# Mach_trai_tim.net
KiCad netlist of a schematic drawn in Altium Designer
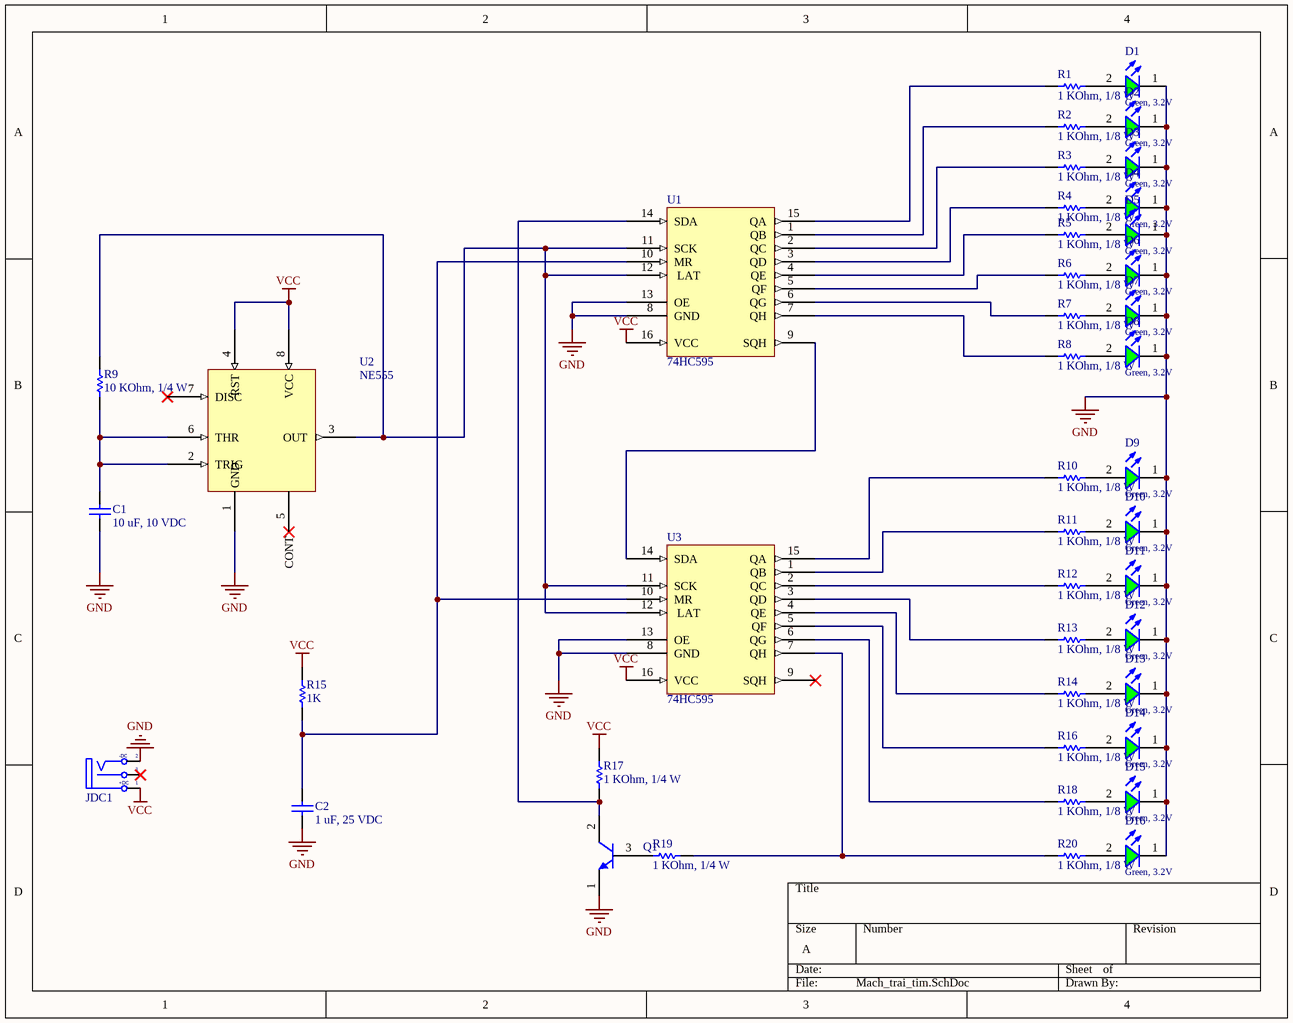
[diagram p0: Mach_trai_tim.SchDoc]

(export (version "E")
  (design (tool "Eeschema 10.0.6"))
  (components
    (comp (ref "C1")
      (value "10 uF, 10 VDC")
      (footprint "CAP_0603")
      (description "CAP, size 0603, 10 uF, 10 VDC")
      (fields (field (name "TOLERANCE") "+/-10%"))
      (libsource (lib "Altium_Ceramic_Cap") (part "0106031061010"))
    )
    (comp (ref "C2")
      (value "1 uF, 25 VDC")
      (footprint "CAP_0603")
      (description "CAP, size 0603, 1 uF, 25 VDC")
      (fields (field (name "TOLERANCE") "+/-10%"))
      (libsource (lib "Altium_Ceramic_Cap") (part "0106031051025"))
    )
    (comp (ref "D1")
      (value "Green, 3.2V")
      (footprint "WL-SMCW_0805")
      (description "WL-SMCW SMT Mono-color Chip LED Waterclear, size 0805, Green, 3.2V, 140deg")
      (libsource (lib "Altium_LED") (part "160805GreenClear"))
    )
    (comp (ref "D2")
      (value "Green, 3.2V")
      (footprint "WL-SMCW_0805")
      (description "WL-SMCW SMT Mono-color Chip LED Waterclear, size 0805, Green, 3.2V, 140deg")
      (libsource (lib "Altium_LED") (part "160805GreenClear"))
    )
    (comp (ref "D3")
      (value "Green, 3.2V")
      (footprint "WL-SMCW_0805")
      (description "WL-SMCW SMT Mono-color Chip LED Waterclear, size 0805, Green, 3.2V, 140deg")
      (libsource (lib "Altium_LED") (part "160805GreenClear"))
    )
    (comp (ref "D4")
      (value "Green, 3.2V")
      (footprint "WL-SMCW_0805")
      (description "WL-SMCW SMT Mono-color Chip LED Waterclear, size 0805, Green, 3.2V, 140deg")
      (libsource (lib "Altium_LED") (part "160805GreenClear"))
    )
    (comp (ref "D5")
      (value "Green, 3.2V")
      (footprint "WL-SMCW_0805")
      (description "WL-SMCW SMT Mono-color Chip LED Waterclear, size 0805, Green, 3.2V, 140deg")
      (libsource (lib "Altium_LED") (part "160805GreenClear"))
    )
    (comp (ref "D6")
      (value "Green, 3.2V")
      (footprint "WL-SMCW_0805")
      (description "WL-SMCW SMT Mono-color Chip LED Waterclear, size 0805, Green, 3.2V, 140deg")
      (libsource (lib "Altium_LED") (part "160805GreenClear"))
    )
    (comp (ref "D7")
      (value "Green, 3.2V")
      (footprint "WL-SMCW_0805")
      (description "WL-SMCW SMT Mono-color Chip LED Waterclear, size 0805, Green, 3.2V, 140deg")
      (libsource (lib "Altium_LED") (part "160805GreenClear"))
    )
    (comp (ref "D8")
      (value "Green, 3.2V")
      (footprint "WL-SMCW_0805")
      (description "WL-SMCW SMT Mono-color Chip LED Waterclear, size 0805, Green, 3.2V, 140deg")
      (libsource (lib "Altium_LED") (part "160805GreenClear"))
    )
    (comp (ref "D9")
      (value "Green, 3.2V")
      (footprint "WL-SMCW_0805")
      (description "WL-SMCW SMT Mono-color Chip LED Waterclear, size 0805, Green, 3.2V, 140deg")
      (libsource (lib "Altium_LED") (part "160805GreenClear"))
    )
    (comp (ref "D10")
      (value "Green, 3.2V")
      (footprint "WL-SMCW_0805")
      (description "WL-SMCW SMT Mono-color Chip LED Waterclear, size 0805, Green, 3.2V, 140deg")
      (libsource (lib "Altium_LED") (part "160805GreenClear"))
    )
    (comp (ref "D11")
      (value "Green, 3.2V")
      (footprint "WL-SMCW_0805")
      (description "WL-SMCW SMT Mono-color Chip LED Waterclear, size 0805, Green, 3.2V, 140deg")
      (libsource (lib "Altium_LED") (part "160805GreenClear"))
    )
    (comp (ref "D12")
      (value "Green, 3.2V")
      (footprint "WL-SMCW_0805")
      (description "WL-SMCW SMT Mono-color Chip LED Waterclear, size 0805, Green, 3.2V, 140deg")
      (libsource (lib "Altium_LED") (part "160805GreenClear"))
    )
    (comp (ref "D13")
      (value "Green, 3.2V")
      (footprint "WL-SMCW_0805")
      (description "WL-SMCW SMT Mono-color Chip LED Waterclear, size 0805, Green, 3.2V, 140deg")
      (libsource (lib "Altium_LED") (part "160805GreenClear"))
    )
    (comp (ref "D14")
      (value "Green, 3.2V")
      (footprint "WL-SMCW_0805")
      (description "WL-SMCW SMT Mono-color Chip LED Waterclear, size 0805, Green, 3.2V, 140deg")
      (libsource (lib "Altium_LED") (part "160805GreenClear"))
    )
    (comp (ref "D15")
      (value "Green, 3.2V")
      (footprint "WL-SMCW_0805")
      (description "WL-SMCW SMT Mono-color Chip LED Waterclear, size 0805, Green, 3.2V, 140deg")
      (libsource (lib "Altium_LED") (part "160805GreenClear"))
    )
    (comp (ref "D16")
      (value "Green, 3.2V")
      (footprint "WL-SMCW_0805")
      (description "WL-SMCW SMT Mono-color Chip LED Waterclear, size 0805, Green, 3.2V, 140deg")
      (libsource (lib "Altium_LED") (part "160805GreenClear"))
    )
    (comp (ref "JDC1")
      (value "Jack DC")
      (footprint "DC-IN")
      (description "Jack DC input")
      (libsource (lib "PIF_Library") (part "Jack DC"))
    )
    (comp (ref "Q1")
      (value "C1815")
      (footprint "SOT23B")
      (description "NPN Bipolar Transistor")
      (libsource (lib "PIF_Library") (part "C1815"))
    )
    (comp (ref "R1")
      (value "1 KOhm, 1/8 W")
      (footprint "RESISTOR_0805")
      (description "RES, size 0805, 1 KOhm, 1/8 W")
      (libsource (lib "Altium_Resistor") (part "0008051021"))
    )
    (comp (ref "R2")
      (value "1 KOhm, 1/8 W")
      (footprint "RESISTOR_0805")
      (description "RES, size 0805, 1 KOhm, 1/8 W")
      (libsource (lib "Altium_Resistor") (part "0008051021"))
    )
    (comp (ref "R3")
      (value "1 KOhm, 1/8 W")
      (footprint "RESISTOR_0805")
      (description "RES, size 0805, 1 KOhm, 1/8 W")
      (libsource (lib "Altium_Resistor") (part "0008051021"))
    )
    (comp (ref "R4")
      (value "1 KOhm, 1/8 W")
      (footprint "RESISTOR_0805")
      (description "RES, size 0805, 1 KOhm, 1/8 W")
      (libsource (lib "Altium_Resistor") (part "0008051021"))
    )
    (comp (ref "R5")
      (value "1 KOhm, 1/8 W")
      (footprint "RESISTOR_0805")
      (description "RES, size 0805, 1 KOhm, 1/8 W")
      (libsource (lib "Altium_Resistor") (part "0008051021"))
    )
    (comp (ref "R6")
      (value "1 KOhm, 1/8 W")
      (footprint "RESISTOR_0805")
      (description "RES, size 0805, 1 KOhm, 1/8 W")
      (libsource (lib "Altium_Resistor") (part "0008051021"))
    )
    (comp (ref "R7")
      (value "1 KOhm, 1/8 W")
      (footprint "RESISTOR_0805")
      (description "RES, size 0805, 1 KOhm, 1/8 W")
      (libsource (lib "Altium_Resistor") (part "0008051021"))
    )
    (comp (ref "R8")
      (value "1 KOhm, 1/8 W")
      (footprint "RESISTOR_0805")
      (description "RES, size 0805, 1 KOhm, 1/8 W")
      (libsource (lib "Altium_Resistor") (part "0008051021"))
    )
    (comp (ref "R9")
      (value "10 KOhm, 1/4 W")
      (footprint "resistor_0603")
      (description "RES, size 0603, 10 KOhm, 1/4 W")
      (libsource (lib "Altium_Resistor") (part "0006031031"))
    )
    (comp (ref "R10")
      (value "1 KOhm, 1/8 W")
      (footprint "RESISTOR_0805")
      (description "RES, size 0805, 1 KOhm, 1/8 W")
      (libsource (lib "Altium_Resistor") (part "0008051021"))
    )
    (comp (ref "R11")
      (value "1 KOhm, 1/8 W")
      (footprint "RESISTOR_0805")
      (description "RES, size 0805, 1 KOhm, 1/8 W")
      (libsource (lib "Altium_Resistor") (part "0008051021"))
    )
    (comp (ref "R12")
      (value "1 KOhm, 1/8 W")
      (footprint "RESISTOR_0805")
      (description "RES, size 0805, 1 KOhm, 1/8 W")
      (libsource (lib "Altium_Resistor") (part "0008051021"))
    )
    (comp (ref "R13")
      (value "1 KOhm, 1/8 W")
      (footprint "RESISTOR_0805")
      (description "RES, size 0805, 1 KOhm, 1/8 W")
      (libsource (lib "Altium_Resistor") (part "0008051021"))
    )
    (comp (ref "R14")
      (value "1 KOhm, 1/8 W")
      (footprint "RESISTOR_0805")
      (description "RES, size 0805, 1 KOhm, 1/8 W")
      (libsource (lib "Altium_Resistor") (part "0008051021"))
    )
    (comp (ref "R15")
      (value "1K")
      (footprint "RES-SM-0603")
      (description "Resistor")
      (fields (field (name "Comment") "RESISTOR SMD"))
      (libsource (lib "PIF_Library") (part "RESISTOR SMD"))
    )
    (comp (ref "R16")
      (value "1 KOhm, 1/8 W")
      (footprint "RESISTOR_0805")
      (description "RES, size 0805, 1 KOhm, 1/8 W")
      (libsource (lib "Altium_Resistor") (part "0008051021"))
    )
    (comp (ref "R17")
      (value "1 KOhm, 1/4 W")
      (footprint "resistor_0603")
      (description "RES, size 0603, 1 KOhm, 1/4 W")
      (libsource (lib "Altium_Resistor") (part "0006031025"))
    )
    (comp (ref "R18")
      (value "1 KOhm, 1/8 W")
      (footprint "RESISTOR_0805")
      (description "RES, size 0805, 1 KOhm, 1/8 W")
      (libsource (lib "Altium_Resistor") (part "0008051021"))
    )
    (comp (ref "R19")
      (value "1 KOhm, 1/4 W")
      (footprint "resistor_0603")
      (description "RES, size 0603, 1 KOhm, 1/4 W")
      (libsource (lib "Altium_Resistor") (part "0006031025"))
    )
    (comp (ref "R20")
      (value "1 KOhm, 1/8 W")
      (footprint "RESISTOR_0805")
      (description "RES, size 0805, 1 KOhm, 1/8 W")
      (libsource (lib "Altium_Resistor") (part "0008051021"))
    )
    (comp (ref "U1")
      (value "74HC595")
      (footprint "74HC595")
      (libsource (lib "Thư_viện_IC_Văn_20_2_2025") (part "74HC595"))
    )
    (comp (ref "U2")
      (value "NE555")
      (footprint "NE555")
      (libsource (lib "Thư_viện_IC_Văn_20_2_2025") (part "NE555"))
    )
    (comp (ref "U3")
      (value "74HC595")
      (footprint "74HC595")
      (libsource (lib "Thư_viện_IC_Văn_20_2_2025") (part "74HC595"))
    )
  )
  (nets
    (net (code "1") (name "GND") (class "Default")
      (node (ref "C1") (pin "1") (pinfunction "1_1") (pintype "passive"))
      (node (ref "C2") (pin "2") (pinfunction "2_2") (pintype "passive"))
      (node (ref "D1") (pin "1") (pinfunction "K_1") (pintype "passive"))
      (node (ref "D10") (pin "1") (pinfunction "K_1") (pintype "passive"))
      (node (ref "D11") (pin "1") (pinfunction "K_1") (pintype "passive"))
      (node (ref "D12") (pin "1") (pinfunction "K_1") (pintype "passive"))
      (node (ref "D13") (pin "1") (pinfunction "K_1") (pintype "passive"))
      (node (ref "D14") (pin "1") (pinfunction "K_1") (pintype "passive"))
      (node (ref "D15") (pin "1") (pinfunction "K_1") (pintype "passive"))
      (node (ref "D16") (pin "1") (pinfunction "K_1") (pintype "passive"))
      (node (ref "D2") (pin "1") (pinfunction "K_1") (pintype "passive"))
      (node (ref "D3") (pin "1") (pinfunction "K_1") (pintype "passive"))
      (node (ref "D4") (pin "1") (pinfunction "K_1") (pintype "passive"))
      (node (ref "D5") (pin "1") (pinfunction "K_1") (pintype "passive"))
      (node (ref "D6") (pin "1") (pinfunction "K_1") (pintype "passive"))
      (node (ref "D7") (pin "1") (pinfunction "K_1") (pintype "passive"))
      (node (ref "D8") (pin "1") (pinfunction "K_1") (pintype "passive"))
      (node (ref "D9") (pin "1") (pinfunction "K_1") (pintype "passive"))
      (node (ref "JDC1") (pin "2") (pinfunction "TN_2") (pintype "passive"))
      (node (ref "Q1") (pin "1") (pinfunction "E_1") (pintype "passive"))
      (node (ref "U1") (pin "13") (pinfunction "OE_13") (pintype "passive"))
      (node (ref "U1") (pin "8") (pinfunction "GND_8") (pintype "power_in"))
      (node (ref "U2") (pin "1") (pinfunction "GND_1") (pintype "power_in"))
      (node (ref "U3") (pin "13") (pinfunction "OE_13") (pintype "passive"))
      (node (ref "U3") (pin "8") (pinfunction "GND_8") (pintype "power_in"))
    )
    (net (code "2") (name "Net-(D1-A)") (class "Default")
      (node (ref "D1") (pin "2") (pinfunction "A_2") (pintype "passive"))
      (node (ref "R1") (pin "2") (pinfunction "2_2") (pintype "passive"))
    )
    (net (code "3") (name "Net-(D2-A)") (class "Default")
      (node (ref "D2") (pin "2") (pinfunction "A_2") (pintype "passive"))
      (node (ref "R2") (pin "2") (pinfunction "2_2") (pintype "passive"))
    )
    (net (code "4") (name "Net-(D3-A)") (class "Default")
      (node (ref "D3") (pin "2") (pinfunction "A_2") (pintype "passive"))
      (node (ref "R3") (pin "2") (pinfunction "2_2") (pintype "passive"))
    )
    (net (code "5") (name "Net-(D4-A)") (class "Default")
      (node (ref "D4") (pin "2") (pinfunction "A_2") (pintype "passive"))
      (node (ref "R4") (pin "2") (pinfunction "2_2") (pintype "passive"))
    )
    (net (code "6") (name "Net-(D5-A)") (class "Default")
      (node (ref "D5") (pin "2") (pinfunction "A_2") (pintype "passive"))
      (node (ref "R5") (pin "2") (pinfunction "2_2") (pintype "passive"))
    )
    (net (code "7") (name "Net-(D6-A)") (class "Default")
      (node (ref "D6") (pin "2") (pinfunction "A_2") (pintype "passive"))
      (node (ref "R6") (pin "2") (pinfunction "2_2") (pintype "passive"))
    )
    (net (code "8") (name "Net-(D7-A)") (class "Default")
      (node (ref "D7") (pin "2") (pinfunction "A_2") (pintype "passive"))
      (node (ref "R7") (pin "2") (pinfunction "2_2") (pintype "passive"))
    )
    (net (code "9") (name "Net-(D8-A)") (class "Default")
      (node (ref "D8") (pin "2") (pinfunction "A_2") (pintype "passive"))
      (node (ref "R8") (pin "2") (pinfunction "2_2") (pintype "passive"))
    )
    (net (code "10") (name "Net-(D9-A)") (class "Default")
      (node (ref "D9") (pin "2") (pinfunction "A_2") (pintype "passive"))
      (node (ref "R10") (pin "2") (pinfunction "2_2") (pintype "passive"))
    )
    (net (code "11") (name "Net-(D10-A)") (class "Default")
      (node (ref "D10") (pin "2") (pinfunction "A_2") (pintype "passive"))
      (node (ref "R11") (pin "2") (pinfunction "2_2") (pintype "passive"))
    )
    (net (code "12") (name "Net-(D11-A)") (class "Default")
      (node (ref "D11") (pin "2") (pinfunction "A_2") (pintype "passive"))
      (node (ref "R12") (pin "2") (pinfunction "2_2") (pintype "passive"))
    )
    (net (code "13") (name "Net-(D12-A)") (class "Default")
      (node (ref "D12") (pin "2") (pinfunction "A_2") (pintype "passive"))
      (node (ref "R13") (pin "2") (pinfunction "2_2") (pintype "passive"))
    )
    (net (code "14") (name "Net-(D13-A)") (class "Default")
      (node (ref "D13") (pin "2") (pinfunction "A_2") (pintype "passive"))
      (node (ref "R14") (pin "2") (pinfunction "2_2") (pintype "passive"))
    )
    (net (code "15") (name "Net-(D14-A)") (class "Default")
      (node (ref "D14") (pin "2") (pinfunction "A_2") (pintype "passive"))
      (node (ref "R16") (pin "2") (pinfunction "2_2") (pintype "passive"))
    )
    (net (code "16") (name "Net-(D15-A)") (class "Default")
      (node (ref "D15") (pin "2") (pinfunction "A_2") (pintype "passive"))
      (node (ref "R18") (pin "2") (pinfunction "2_2") (pintype "passive"))
    )
    (net (code "17") (name "Net-(D16-A)") (class "Default")
      (node (ref "D16") (pin "2") (pinfunction "A_2") (pintype "passive"))
      (node (ref "R20") (pin "2") (pinfunction "2_2") (pintype "passive"))
    )
    (net (code "18") (name "Net-(Q1-B)") (class "Default")
      (node (ref "Q1") (pin "3") (pinfunction "B_3") (pintype "passive"))
      (node (ref "R19") (pin "1") (pinfunction "1_1") (pintype "passive"))
    )
    (net (code "19") (name "Net-(Q1-C)") (class "Default")
      (node (ref "Q1") (pin "2") (pinfunction "C_2") (pintype "passive"))
      (node (ref "R17") (pin "1") (pinfunction "1_1") (pintype "passive"))
      (node (ref "U1") (pin "14") (pinfunction "SDA_14") (pintype "input"))
    )
    (net (code "20") (name "Net-(U1-MR)") (class "Default")
      (node (ref "C2") (pin "1") (pinfunction "1_1") (pintype "passive"))
      (node (ref "R15") (pin "1") (pinfunction "1_1") (pintype "passive"))
      (node (ref "U1") (pin "10") (pinfunction "MR_10") (pintype "input"))
      (node (ref "U3") (pin "10") (pinfunction "MR_10") (pintype "input"))
    )
    (net (code "21") (name "Net-(U1-QA)") (class "Default")
      (node (ref "R1") (pin "1") (pinfunction "1_1") (pintype "passive"))
      (node (ref "U1") (pin "15") (pinfunction "QA_15") (pintype "output"))
    )
    (net (code "22") (name "Net-(U1-QB)") (class "Default")
      (node (ref "R2") (pin "1") (pinfunction "1_1") (pintype "passive"))
      (node (ref "U1") (pin "1") (pinfunction "QB_1") (pintype "output"))
    )
    (net (code "23") (name "Net-(U1-QC)") (class "Default")
      (node (ref "R3") (pin "1") (pinfunction "1_1") (pintype "passive"))
      (node (ref "U1") (pin "2") (pinfunction "QC_2") (pintype "output"))
    )
    (net (code "24") (name "Net-(U1-QD)") (class "Default")
      (node (ref "R4") (pin "1") (pinfunction "1_1") (pintype "passive"))
      (node (ref "U1") (pin "3") (pinfunction "QD_3") (pintype "output"))
    )
    (net (code "25") (name "Net-(U1-QE)") (class "Default")
      (node (ref "R5") (pin "1") (pinfunction "1_1") (pintype "passive"))
      (node (ref "U1") (pin "4") (pinfunction "QE_4") (pintype "output"))
    )
    (net (code "26") (name "Net-(U1-QF)") (class "Default")
      (node (ref "R6") (pin "1") (pinfunction "1_1") (pintype "passive"))
      (node (ref "U1") (pin "5") (pinfunction "QF_5") (pintype "output"))
    )
    (net (code "27") (name "Net-(U1-QG)") (class "Default")
      (node (ref "R7") (pin "1") (pinfunction "1_1") (pintype "passive"))
      (node (ref "U1") (pin "6") (pinfunction "QG_6") (pintype "output"))
    )
    (net (code "28") (name "Net-(U1-QH)") (class "Default")
      (node (ref "R8") (pin "1") (pinfunction "1_1") (pintype "passive"))
      (node (ref "U1") (pin "7") (pinfunction "QH_7") (pintype "output"))
    )
    (net (code "29") (name "Net-(U1-SCK)") (class "Default")
      (node (ref "R9") (pin "2") (pinfunction "2_2") (pintype "passive"))
      (node (ref "U1") (pin "11") (pinfunction "SCK_11") (pintype "input"))
      (node (ref "U1") (pin "12") (pinfunction "_LAT_12") (pintype "input"))
      (node (ref "U2") (pin "3") (pinfunction "OUT_3") (pintype "output"))
      (node (ref "U3") (pin "11") (pinfunction "SCK_11") (pintype "input"))
      (node (ref "U3") (pin "12") (pinfunction "_LAT_12") (pintype "input"))
    )
    (net (code "30") (name "Net-(U1-SQH)") (class "Default")
      (node (ref "U1") (pin "9") (pinfunction "SQH_9") (pintype "output"))
      (node (ref "U3") (pin "14") (pinfunction "SDA_14") (pintype "input"))
    )
    (net (code "31") (name "Net-(U2-THR)") (class "Default")
      (node (ref "C1") (pin "2") (pinfunction "2_2") (pintype "passive"))
      (node (ref "R9") (pin "1") (pinfunction "1_1") (pintype "passive"))
      (node (ref "U2") (pin "2") (pinfunction "TRIG_2") (pintype "input"))
      (node (ref "U2") (pin "6") (pinfunction "THR_6") (pintype "input"))
    )
    (net (code "32") (name "Net-(U3-QA)") (class "Default")
      (node (ref "R10") (pin "1") (pinfunction "1_1") (pintype "passive"))
      (node (ref "U3") (pin "15") (pinfunction "QA_15") (pintype "output"))
    )
    (net (code "33") (name "Net-(U3-QB)") (class "Default")
      (node (ref "R11") (pin "1") (pinfunction "1_1") (pintype "passive"))
      (node (ref "U3") (pin "1") (pinfunction "QB_1") (pintype "output"))
    )
    (net (code "34") (name "Net-(U3-QC)") (class "Default")
      (node (ref "R12") (pin "1") (pinfunction "1_1") (pintype "passive"))
      (node (ref "U3") (pin "2") (pinfunction "QC_2") (pintype "output"))
    )
    (net (code "35") (name "Net-(U3-QD)") (class "Default")
      (node (ref "R13") (pin "1") (pinfunction "1_1") (pintype "passive"))
      (node (ref "U3") (pin "3") (pinfunction "QD_3") (pintype "output"))
    )
    (net (code "36") (name "Net-(U3-QE)") (class "Default")
      (node (ref "R14") (pin "1") (pinfunction "1_1") (pintype "passive"))
      (node (ref "U3") (pin "4") (pinfunction "QE_4") (pintype "output"))
    )
    (net (code "37") (name "Net-(U3-QF)") (class "Default")
      (node (ref "R16") (pin "1") (pinfunction "1_1") (pintype "passive"))
      (node (ref "U3") (pin "5") (pinfunction "QF_5") (pintype "output"))
    )
    (net (code "38") (name "Net-(U3-QG)") (class "Default")
      (node (ref "R18") (pin "1") (pinfunction "1_1") (pintype "passive"))
      (node (ref "U3") (pin "6") (pinfunction "QG_6") (pintype "output"))
    )
    (net (code "39") (name "Net-(U3-QH)") (class "Default")
      (node (ref "R19") (pin "2") (pinfunction "2_2") (pintype "passive"))
      (node (ref "R20") (pin "1") (pinfunction "1_1") (pintype "passive"))
      (node (ref "U3") (pin "7") (pinfunction "QH_7") (pintype "output"))
    )
    (net (code "40") (name "VCC") (class "Default")
      (node (ref "JDC1") (pin "1") (pinfunction "T_1") (pintype "passive"))
      (node (ref "R15") (pin "2") (pinfunction "2_2") (pintype "passive"))
      (node (ref "R17") (pin "2") (pinfunction "2_2") (pintype "passive"))
      (node (ref "U1") (pin "16") (pinfunction "VCC_16") (pintype "input"))
      (node (ref "U2") (pin "4") (pinfunction "RST_4") (pintype "input"))
      (node (ref "U2") (pin "8") (pinfunction "VCC_8") (pintype "input"))
      (node (ref "U3") (pin "16") (pinfunction "VCC_16") (pintype "input"))
    )
    (net (code "41") (name "unconnected-(JDC1-S-Pad3)") (class "Default")
      (node (ref "JDC1") (pin "3") (pinfunction "S_3") (pintype "power_in+no_connect"))
    )
    (net (code "42") (name "unconnected-(U2-CONT-Pad5)") (class "Default")
      (node (ref "U2") (pin "5") (pinfunction "CONT_5") (pintype "passive"))
    )
    (net (code "43") (name "unconnected-(U2-DISC-Pad7)") (class "Default")
      (node (ref "U2") (pin "7") (pinfunction "DISC_7") (pintype "input+no_connect"))
    )
    (net (code "44") (name "unconnected-(U3-SQH-Pad9)") (class "Default")
      (node (ref "U3") (pin "9") (pinfunction "SQH_9") (pintype "output+no_connect"))
    )
  )
)
